# ESP32_breakout_v2.net
KiCad netlist of a schematic drawn in EAGLE
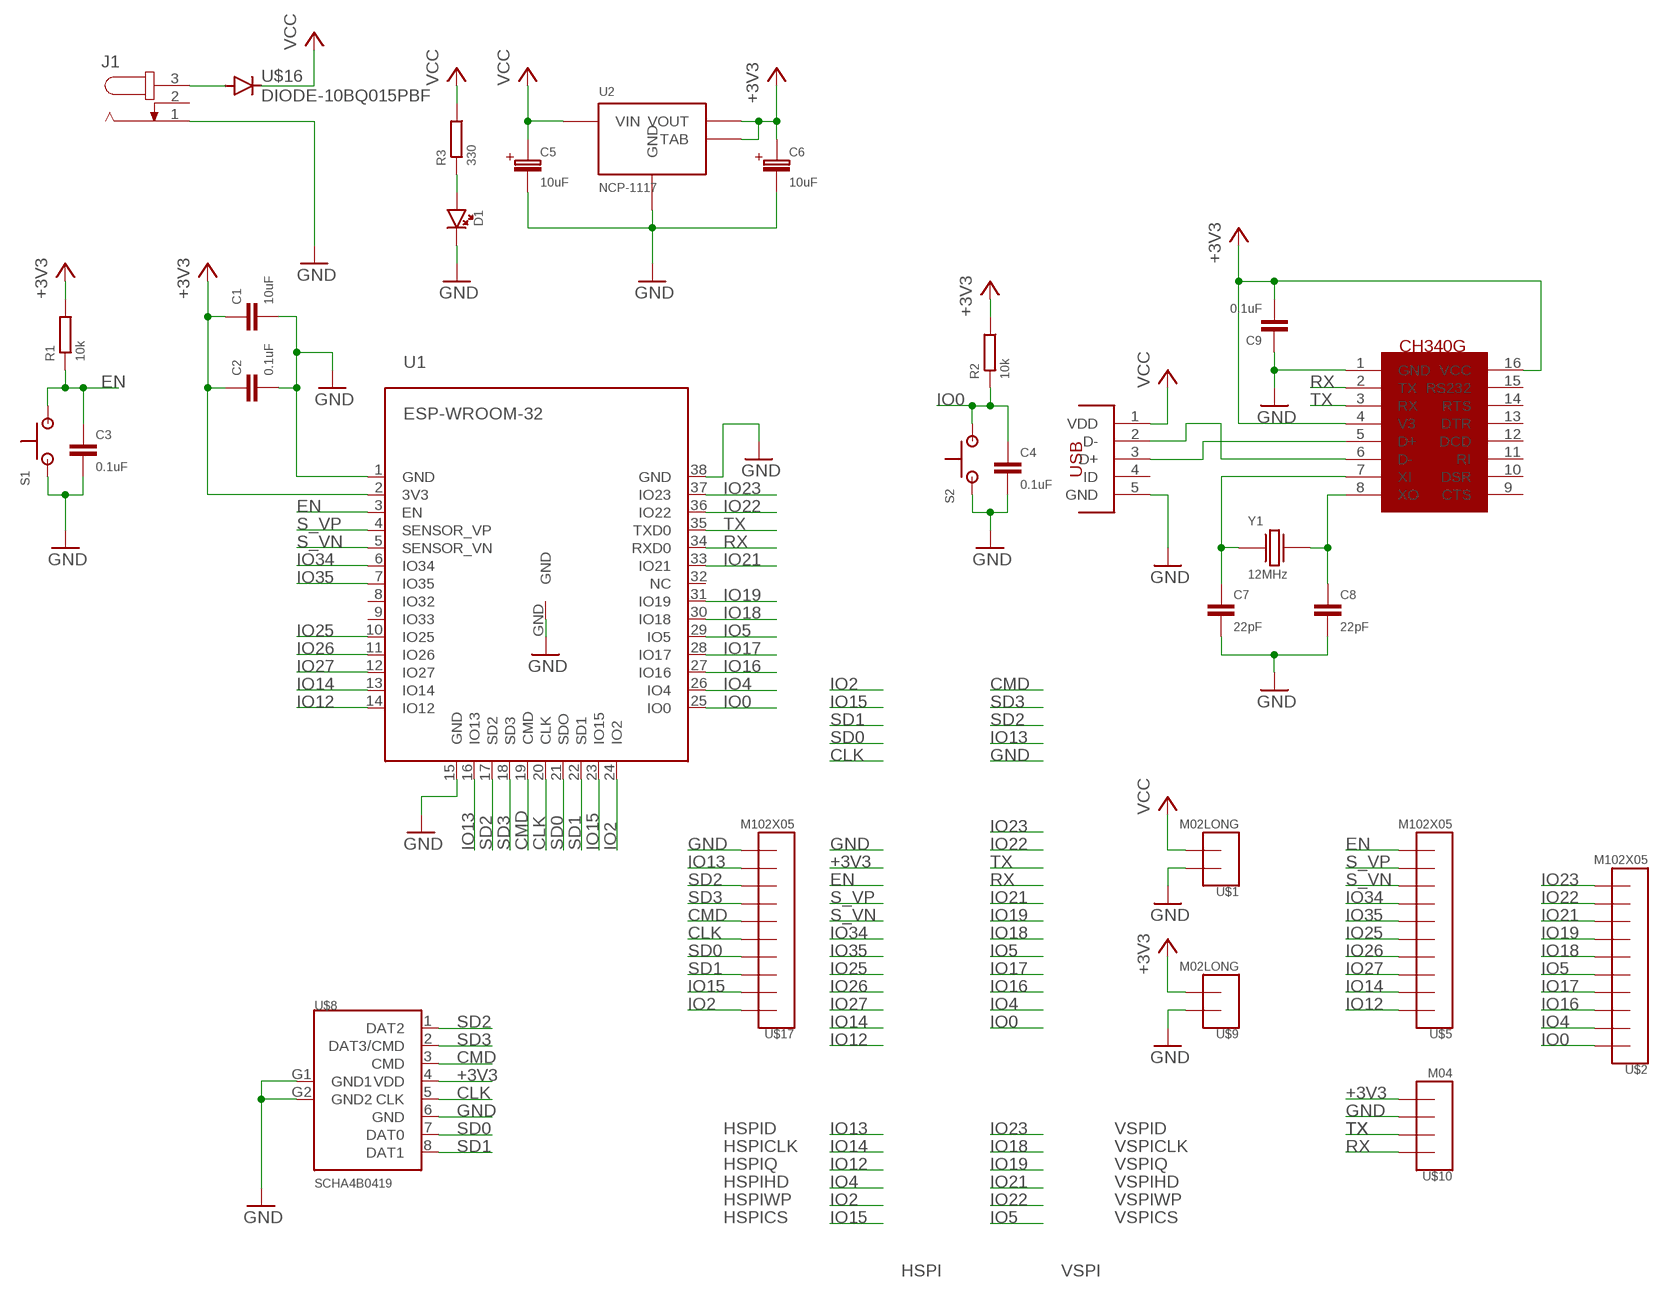
[diagram p0: schematic, sheet 1]

(export (version "E")
  (design (tool "Eeschema 10.0.6"))
  (components
    (comp (ref "C1")
      (value "10uF")
      (footprint "eagle-import:CAP-0603")
      (libsource (lib "eagle-import") (part "CAP0603"))
    )
    (comp (ref "C2")
      (value "0.1uF")
      (footprint "eagle-import:CAP-0603")
      (libsource (lib "eagle-import") (part "CAP0603"))
    )
    (comp (ref "C3")
      (value "0.1uF")
      (footprint "eagle-import:CAP-0603")
      (libsource (lib "eagle-import") (part "CAP0603"))
    )
    (comp (ref "C4")
      (value "0.1uF")
      (footprint "eagle-import:CAP-0603")
      (libsource (lib "eagle-import") (part "CAP0603"))
    )
    (comp (ref "C5")
      (value "10uF")
      (footprint "eagle-import:B-3528")
      (libsource (lib "eagle-import") (part "CAP-POLARCASEB-3528"))
    )
    (comp (ref "C6")
      (value "10uF")
      (footprint "eagle-import:B-3528")
      (libsource (lib "eagle-import") (part "CAP-POLARCASEB-3528"))
    )
    (comp (ref "C7")
      (value "22pF")
      (footprint "eagle-import:CAP-0603")
      (libsource (lib "eagle-import") (part "CAP0603"))
    )
    (comp (ref "C8")
      (value "22pF")
      (footprint "eagle-import:CAP-0603")
      (libsource (lib "eagle-import") (part "CAP0603"))
    )
    (comp (ref "C9")
      (value "0.1uF")
      (footprint "eagle-import:CAP-0603")
      (libsource (lib "eagle-import") (part "CAP0603"))
    )
    (comp (ref "D1")
      (value "LED1206")
      (footprint "eagle-import:LED-1206")
      (libsource (lib "eagle-import") (part "LED1206"))
    )
    (comp (ref "J1")
      (value "JACK-PLUG0")
      (footprint "eagle-import:SPC4077")
      (libsource (lib "eagle-import") (part "JACK-PLUG0"))
    )
    (comp (ref "R1")
      (value "10k")
      (footprint "eagle-import:RES-0603")
      (libsource (lib "eagle-import") (part "RESISTOR0603"))
    )
    (comp (ref "R2")
      (value "10k")
      (footprint "eagle-import:RES-0603")
      (libsource (lib "eagle-import") (part "RESISTOR0603"))
    )
    (comp (ref "R3")
      (value "330")
      (footprint "eagle-import:RES-0603")
      (libsource (lib "eagle-import") (part "RESISTOR0603"))
    )
    (comp (ref "S1")
      (value "PUSHBUTTONSKHMQME010")
      (footprint "eagle-import:SKHMQME010")
      (libsource (lib "eagle-import") (part "PUSHBUTTONSKHMQME010"))
    )
    (comp (ref "S2")
      (value "PUSHBUTTONSKHMQME010")
      (footprint "eagle-import:SKHMQME010")
      (libsource (lib "eagle-import") (part "PUSHBUTTONSKHMQME010"))
    )
    (comp (ref "U$1")
      (value "M02LONG")
      (footprint "eagle-import:1X02-LONG")
      (libsource (lib "eagle-import") (part "M02LONG"))
    )
    (comp (ref "U$2")
      (value "M102X05")
      (footprint "eagle-import:2X05")
      (libsource (lib "eagle-import") (part "M102X05"))
    )
    (comp (ref "U$4")
      (value "MOLEX_USBMICRO")
      (footprint "eagle-import:MOLEX_47346-001")
      (libsource (lib "eagle-import") (part "MOLEX_USBMICRO"))
    )
    (comp (ref "U$5")
      (value "M102X05")
      (footprint "eagle-import:2X05")
      (libsource (lib "eagle-import") (part "M102X05"))
    )
    (comp (ref "U$7")
      (value "CH340G")
      (footprint "eagle-import:SOIC16")
      (libsource (lib "eagle-import") (part "CH340G"))
    )
    (comp (ref "U$8")
      (value "SCHA4B0419")
      (footprint "eagle-import:MICROSD_SCHA4B0419")
      (libsource (lib "eagle-import") (part "SCHA4B0419"))
    )
    (comp (ref "U$9")
      (value "M02LONG")
      (footprint "eagle-import:1X02-LONG")
      (libsource (lib "eagle-import") (part "M02LONG"))
    )
    (comp (ref "U$10")
      (value "M04")
      (footprint "eagle-import:1X04")
      (libsource (lib "eagle-import") (part "M04"))
    )
    (comp (ref "U$16")
      (value "DIODE-10BQ015PBF")
      (footprint "eagle-import:10BQ015PB")
      (libsource (lib "eagle-import") (part "DIODE-10BQ015PBF"))
    )
    (comp (ref "U$17")
      (value "M102X05")
      (footprint "eagle-import:2X05")
      (libsource (lib "eagle-import") (part "M102X05"))
    )
    (comp (ref "U1")
      (value "ESP-WROOM-32")
      (footprint "eagle-import:ESP-WROOM-32")
      (libsource (lib "eagle-import") (part "ESP-WROOM-32"))
    )
    (comp (ref "U2")
      (value "NCP-1117")
      (footprint "eagle-import:SOT-223-4")
      (libsource (lib "eagle-import") (part "NCP-1117"))
    )
    (comp (ref "Y1")
      (value "12MHz")
      (footprint "eagle-import:HC-49_US")
      (libsource (lib "eagle-import") (part "ABLS-12MHZ-B2-T"))
    )
  )
  (nets
    (net (code "1") (name "+3V3") (class "Default")
      (node (ref "C1") (pin "1") (pinfunction "1_1") (pintype "passive"))
      (node (ref "C2") (pin "1") (pinfunction "1_1") (pintype "passive"))
      (node (ref "C6") (pin "P") (pinfunction "P_P") (pintype "passive"))
      (node (ref "C9") (pin "2") (pinfunction "2_2") (pintype "passive"))
      (node (ref "R1") (pin "2") (pinfunction "2_2") (pintype "passive"))
      (node (ref "R2") (pin "2") (pinfunction "2_2") (pintype "passive"))
      (node (ref "U$10") (pin "4") (pinfunction "4_4") (pintype "bidirectional"))
      (node (ref "U$7") (pin "16") (pinfunction "VCC_16") (pintype "bidirectional"))
      (node (ref "U$7") (pin "4") (pinfunction "V3_4") (pintype "bidirectional"))
      (node (ref "U$8") (pin "4") (pinfunction "VDD_4") (pintype "bidirectional"))
      (node (ref "U$9") (pin "2") (pinfunction "2_2") (pintype "bidirectional"))
      (node (ref "U1") (pin "2") (pinfunction "3V3_2") (pintype "bidirectional"))
      (node (ref "U2") (pin "2") (pinfunction "VOUT_2") (pintype "power_in"))
      (node (ref "U2") (pin "PAD") (pinfunction "TAB_PAD") (pintype "power_in"))
    )
    (net (code "2") (name "/CLK") (class "Default")
      (node (ref "U$17") (pin "5") (pinfunction "5_5") (pintype "bidirectional"))
      (node (ref "U$8") (pin "5") (pinfunction "CLK_5") (pintype "bidirectional"))
      (node (ref "U1") (pin "20") (pinfunction "CLK_20") (pintype "bidirectional"))
    )
    (net (code "3") (name "/CMD") (class "Default")
      (node (ref "U$17") (pin "6") (pinfunction "6_6") (pintype "bidirectional"))
      (node (ref "U$8") (pin "3") (pinfunction "CMD_3") (pintype "bidirectional"))
      (node (ref "U1") (pin "19") (pinfunction "CMD_19") (pintype "bidirectional"))
    )
    (net (code "4") (name "/EN") (class "Default")
      (node (ref "C3") (pin "1") (pinfunction "1_1") (pintype "passive"))
      (node (ref "R1") (pin "1") (pinfunction "1_1") (pintype "passive"))
      (node (ref "S1") (pin "3") (pinfunction "2_3") (pintype "bidirectional"))
      (node (ref "S1") (pin "4") (pinfunction "2_4") (pintype "bidirectional"))
      (node (ref "U$5") (pin "10") (pinfunction "10_10") (pintype "bidirectional"))
      (node (ref "U1") (pin "3") (pinfunction "EN_3") (pintype "bidirectional"))
    )
    (net (code "5") (name "/IO0") (class "Default")
      (node (ref "C4") (pin "1") (pinfunction "1_1") (pintype "passive"))
      (node (ref "R2") (pin "1") (pinfunction "1_1") (pintype "passive"))
      (node (ref "S2") (pin "3") (pinfunction "2_3") (pintype "bidirectional"))
      (node (ref "S2") (pin "4") (pinfunction "2_4") (pintype "bidirectional"))
      (node (ref "U$2") (pin "1") (pinfunction "1_1") (pintype "bidirectional"))
      (node (ref "U1") (pin "25") (pinfunction "IO0_25") (pintype "bidirectional"))
    )
    (net (code "6") (name "/IO2") (class "Default")
      (node (ref "U$17") (pin "1") (pinfunction "1_1") (pintype "bidirectional"))
      (node (ref "U1") (pin "24") (pinfunction "IO2_24") (pintype "bidirectional"))
    )
    (net (code "7") (name "/IO4") (class "Default")
      (node (ref "U$2") (pin "2") (pinfunction "2_2") (pintype "bidirectional"))
      (node (ref "U1") (pin "26") (pinfunction "IO4_26") (pintype "bidirectional"))
    )
    (net (code "8") (name "/IO5") (class "Default")
      (node (ref "U$2") (pin "5") (pinfunction "5_5") (pintype "bidirectional"))
      (node (ref "U1") (pin "29") (pinfunction "IO5_29") (pintype "bidirectional"))
    )
    (net (code "9") (name "/IO12") (class "Default")
      (node (ref "U$5") (pin "1") (pinfunction "1_1") (pintype "bidirectional"))
      (node (ref "U1") (pin "14") (pinfunction "IO12_14") (pintype "bidirectional"))
    )
    (net (code "10") (name "/IO13") (class "Default")
      (node (ref "U$17") (pin "9") (pinfunction "9_9") (pintype "bidirectional"))
      (node (ref "U1") (pin "16") (pinfunction "IO13_16") (pintype "bidirectional"))
    )
    (net (code "11") (name "/IO14") (class "Default")
      (node (ref "U$5") (pin "2") (pinfunction "2_2") (pintype "bidirectional"))
      (node (ref "U1") (pin "13") (pinfunction "IO14_13") (pintype "bidirectional"))
    )
    (net (code "12") (name "/IO15") (class "Default")
      (node (ref "U$17") (pin "2") (pinfunction "2_2") (pintype "bidirectional"))
      (node (ref "U1") (pin "23") (pinfunction "IO15_23") (pintype "bidirectional"))
    )
    (net (code "13") (name "/IO16") (class "Default")
      (node (ref "U$2") (pin "3") (pinfunction "3_3") (pintype "bidirectional"))
      (node (ref "U1") (pin "27") (pinfunction "IO16_27") (pintype "bidirectional"))
    )
    (net (code "14") (name "/IO17") (class "Default")
      (node (ref "U$2") (pin "4") (pinfunction "4_4") (pintype "bidirectional"))
      (node (ref "U1") (pin "28") (pinfunction "IO17_28") (pintype "bidirectional"))
    )
    (net (code "15") (name "/IO18") (class "Default")
      (node (ref "U$2") (pin "6") (pinfunction "6_6") (pintype "bidirectional"))
      (node (ref "U1") (pin "30") (pinfunction "IO18_30") (pintype "bidirectional"))
    )
    (net (code "16") (name "/IO19") (class "Default")
      (node (ref "U$2") (pin "7") (pinfunction "7_7") (pintype "bidirectional"))
      (node (ref "U1") (pin "31") (pinfunction "IO19_31") (pintype "bidirectional"))
    )
    (net (code "17") (name "/IO21") (class "Default")
      (node (ref "U$2") (pin "8") (pinfunction "8_8") (pintype "bidirectional"))
      (node (ref "U1") (pin "33") (pinfunction "IO21_33") (pintype "bidirectional"))
    )
    (net (code "18") (name "/IO22") (class "Default")
      (node (ref "U$2") (pin "9") (pinfunction "9_9") (pintype "bidirectional"))
      (node (ref "U1") (pin "36") (pinfunction "IO22_36") (pintype "bidirectional"))
    )
    (net (code "19") (name "/IO23") (class "Default")
      (node (ref "U$2") (pin "10") (pinfunction "10_10") (pintype "bidirectional"))
      (node (ref "U1") (pin "37") (pinfunction "IO23_37") (pintype "bidirectional"))
    )
    (net (code "20") (name "/IO25") (class "Default")
      (node (ref "U$5") (pin "5") (pinfunction "5_5") (pintype "bidirectional"))
      (node (ref "U1") (pin "10") (pinfunction "IO25_10") (pintype "bidirectional"))
    )
    (net (code "21") (name "/IO26") (class "Default")
      (node (ref "U$5") (pin "4") (pinfunction "4_4") (pintype "bidirectional"))
      (node (ref "U1") (pin "11") (pinfunction "IO26_11") (pintype "bidirectional"))
    )
    (net (code "22") (name "/IO27") (class "Default")
      (node (ref "U$5") (pin "3") (pinfunction "3_3") (pintype "bidirectional"))
      (node (ref "U1") (pin "12") (pinfunction "IO27_12") (pintype "bidirectional"))
    )
    (net (code "23") (name "/IO34") (class "Default")
      (node (ref "U$5") (pin "7") (pinfunction "7_7") (pintype "bidirectional"))
      (node (ref "U1") (pin "6") (pinfunction "IO34_6") (pintype "bidirectional"))
    )
    (net (code "24") (name "/IO35") (class "Default")
      (node (ref "U$5") (pin "6") (pinfunction "6_6") (pintype "bidirectional"))
      (node (ref "U1") (pin "7") (pinfunction "IO35_7") (pintype "bidirectional"))
    )
    (net (code "25") (name "/RX") (class "Default")
      (node (ref "U$10") (pin "1") (pinfunction "1_1") (pintype "bidirectional"))
      (node (ref "U$7") (pin "2") (pinfunction "TX_2") (pintype "bidirectional"))
      (node (ref "U1") (pin "34") (pinfunction "RXD0_34") (pintype "bidirectional"))
    )
    (net (code "26") (name "/SD0") (class "Default")
      (node (ref "U$17") (pin "4") (pinfunction "4_4") (pintype "bidirectional"))
      (node (ref "U$8") (pin "7") (pinfunction "DAT0_7") (pintype "bidirectional"))
      (node (ref "U1") (pin "21") (pinfunction "SDO_21") (pintype "bidirectional"))
    )
    (net (code "27") (name "/SD1") (class "Default")
      (node (ref "U$17") (pin "3") (pinfunction "3_3") (pintype "bidirectional"))
      (node (ref "U$8") (pin "8") (pinfunction "DAT1_8") (pintype "bidirectional"))
      (node (ref "U1") (pin "22") (pinfunction "SD1_22") (pintype "bidirectional"))
    )
    (net (code "28") (name "/SD2") (class "Default")
      (node (ref "U$17") (pin "8") (pinfunction "8_8") (pintype "bidirectional"))
      (node (ref "U$8") (pin "1") (pinfunction "DAT2_1") (pintype "bidirectional"))
      (node (ref "U1") (pin "17") (pinfunction "SD2_17") (pintype "bidirectional"))
    )
    (net (code "29") (name "/SD3") (class "Default")
      (node (ref "U$17") (pin "7") (pinfunction "7_7") (pintype "bidirectional"))
      (node (ref "U$8") (pin "2") (pinfunction "DAT3/CMD_2") (pintype "bidirectional"))
      (node (ref "U1") (pin "18") (pinfunction "SD3_18") (pintype "bidirectional"))
    )
    (net (code "30") (name "/S_VN") (class "Default")
      (node (ref "U$5") (pin "8") (pinfunction "8_8") (pintype "bidirectional"))
      (node (ref "U1") (pin "5") (pinfunction "SENSOR_VN_5") (pintype "bidirectional"))
    )
    (net (code "31") (name "/S_VP") (class "Default")
      (node (ref "U$5") (pin "9") (pinfunction "9_9") (pintype "bidirectional"))
      (node (ref "U1") (pin "4") (pinfunction "SENSOR_VP_4") (pintype "bidirectional"))
    )
    (net (code "32") (name "/TX") (class "Default")
      (node (ref "U$10") (pin "2") (pinfunction "2_2") (pintype "bidirectional"))
      (node (ref "U$7") (pin "3") (pinfunction "RX_3") (pintype "bidirectional"))
      (node (ref "U1") (pin "35") (pinfunction "TXD0_35") (pintype "bidirectional"))
    )
    (net (code "33") (name "GND") (class "Default")
      (node (ref "C1") (pin "2") (pinfunction "2_2") (pintype "passive"))
      (node (ref "C2") (pin "2") (pinfunction "2_2") (pintype "passive"))
      (node (ref "C3") (pin "2") (pinfunction "2_2") (pintype "passive"))
      (node (ref "C4") (pin "2") (pinfunction "2_2") (pintype "passive"))
      (node (ref "C5") (pin "N") (pinfunction "N_N") (pintype "passive"))
      (node (ref "C6") (pin "N") (pinfunction "N_N") (pintype "passive"))
      (node (ref "C7") (pin "2") (pinfunction "2_2") (pintype "passive"))
      (node (ref "C8") (pin "2") (pinfunction "2_2") (pintype "passive"))
      (node (ref "C9") (pin "1") (pinfunction "1_1") (pintype "passive"))
      (node (ref "D1") (pin "C") (pinfunction "C_C") (pintype "bidirectional"))
      (node (ref "J1") (pin "1") (pinfunction "1_1") (pintype "passive"))
      (node (ref "S1") (pin "1") (pinfunction "1_1") (pintype "bidirectional"))
      (node (ref "S1") (pin "2") (pinfunction "1_2") (pintype "bidirectional"))
      (node (ref "S2") (pin "1") (pinfunction "1_1") (pintype "bidirectional"))
      (node (ref "S2") (pin "2") (pinfunction "1_2") (pintype "bidirectional"))
      (node (ref "U$1") (pin "1") (pinfunction "1_1") (pintype "bidirectional"))
      (node (ref "U$10") (pin "3") (pinfunction "3_3") (pintype "bidirectional"))
      (node (ref "U$17") (pin "10") (pinfunction "10_10") (pintype "bidirectional"))
      (node (ref "U$4") (pin "5") (pinfunction "GND_5") (pintype "bidirectional"))
      (node (ref "U$7") (pin "1") (pinfunction "GND_1") (pintype "bidirectional"))
      (node (ref "U$8") (pin "6") (pinfunction "GND_6") (pintype "bidirectional"))
      (node (ref "U$8") (pin "G1") (pinfunction "GND1_G1") (pintype "bidirectional"))
      (node (ref "U$8") (pin "G2") (pinfunction "GND2_G2") (pintype "bidirectional"))
      (node (ref "U$9") (pin "1") (pinfunction "1_1") (pintype "bidirectional"))
      (node (ref "U1") (pin "1") (pinfunction "GND_1") (pintype "bidirectional"))
      (node (ref "U1") (pin "15") (pinfunction "GND_15") (pintype "bidirectional"))
      (node (ref "U1") (pin "38") (pinfunction "GND_38") (pintype "bidirectional"))
      (node (ref "U1") (pin "GND") (pinfunction "GND_GND") (pintype "bidirectional"))
      (node (ref "U2") (pin "1") (pinfunction "GND_1") (pintype "power_in"))
    )
    (net (code "34") (name "Net-(D1-PadA)") (class "Default")
      (node (ref "D1") (pin "A") (pinfunction "A_A") (pintype "bidirectional"))
      (node (ref "R3") (pin "1") (pinfunction "1_1") (pintype "passive"))
    )
    (net (code "35") (name "Net-(J1-Pad3)") (class "Default")
      (node (ref "J1") (pin "3") (pinfunction "3_3") (pintype "passive"))
      (node (ref "U$16") (pin "A") (pinfunction "A_A") (pintype "passive"))
    )
    (net (code "36") (name "Net-(U$4-D+)") (class "Default")
      (node (ref "U$4") (pin "3") (pinfunction "D+_3") (pintype "bidirectional"))
      (node (ref "U$7") (pin "5") (pinfunction "D+_5") (pintype "bidirectional"))
    )
    (net (code "37") (name "Net-(U$4-D-)") (class "Default")
      (node (ref "U$4") (pin "2") (pinfunction "D-_2") (pintype "bidirectional"))
      (node (ref "U$7") (pin "6") (pinfunction "D-_6") (pintype "bidirectional"))
    )
    (net (code "38") (name "Net-(U$7-XI)") (class "Default")
      (node (ref "C7") (pin "1") (pinfunction "1_1") (pintype "passive"))
      (node (ref "U$7") (pin "7") (pinfunction "XI_7") (pintype "bidirectional"))
      (node (ref "Y1") (pin "P$1") (pinfunction "1_P$1") (pintype "bidirectional"))
    )
    (net (code "39") (name "Net-(U$7-XO)") (class "Default")
      (node (ref "C8") (pin "1") (pinfunction "1_1") (pintype "passive"))
      (node (ref "U$7") (pin "8") (pinfunction "XO_8") (pintype "bidirectional"))
      (node (ref "Y1") (pin "P$2") (pinfunction "2_P$2") (pintype "bidirectional"))
    )
    (net (code "40") (name "VCC") (class "Default")
      (node (ref "C5") (pin "P") (pinfunction "P_P") (pintype "passive"))
      (node (ref "R3") (pin "2") (pinfunction "2_2") (pintype "passive"))
      (node (ref "U$1") (pin "2") (pinfunction "2_2") (pintype "bidirectional"))
      (node (ref "U$16") (pin "C") (pinfunction "C_C") (pintype "passive"))
      (node (ref "U$4") (pin "1") (pinfunction "VDD_1") (pintype "bidirectional"))
      (node (ref "U2") (pin "3") (pinfunction "VIN_3") (pintype "power_in"))
    )
    (net (code "41") (name "unconnected-(J1-Pad2)") (class "Default")
      (node (ref "J1") (pin "2") (pinfunction "2_2") (pintype "passive"))
    )
    (net (code "42") (name "unconnected-(S1-3-Pad5)") (class "Default")
      (node (ref "S1") (pin "5") (pinfunction "3_5") (pintype "bidirectional"))
    )
    (net (code "43") (name "unconnected-(S2-3-Pad5)") (class "Default")
      (node (ref "S2") (pin "5") (pinfunction "3_5") (pintype "bidirectional"))
    )
    (net (code "44") (name "unconnected-(U$4-ID-Pad4)") (class "Default")
      (node (ref "U$4") (pin "4") (pinfunction "ID_4") (pintype "bidirectional"))
    )
    (net (code "45") (name "unconnected-(U$7-CTS-Pad9)") (class "Default")
      (node (ref "U$7") (pin "9") (pinfunction "CTS_9") (pintype "bidirectional"))
    )
    (net (code "46") (name "unconnected-(U$7-DCD-Pad12)") (class "Default")
      (node (ref "U$7") (pin "12") (pinfunction "DCD_12") (pintype "bidirectional"))
    )
    (net (code "47") (name "unconnected-(U$7-DSR-Pad10)") (class "Default")
      (node (ref "U$7") (pin "10") (pinfunction "DSR_10") (pintype "bidirectional"))
    )
    (net (code "48") (name "unconnected-(U$7-DTR-Pad13)") (class "Default")
      (node (ref "U$7") (pin "13") (pinfunction "DTR_13") (pintype "bidirectional"))
    )
    (net (code "49") (name "unconnected-(U$7-RI-Pad11)") (class "Default")
      (node (ref "U$7") (pin "11") (pinfunction "RI_11") (pintype "bidirectional"))
    )
    (net (code "50") (name "unconnected-(U$7-RS232-Pad15)") (class "Default")
      (node (ref "U$7") (pin "15") (pinfunction "RS232_15") (pintype "bidirectional"))
    )
    (net (code "51") (name "unconnected-(U$7-RTS-Pad14)") (class "Default")
      (node (ref "U$7") (pin "14") (pinfunction "RTS_14") (pintype "bidirectional"))
    )
    (net (code "52") (name "unconnected-(U1-IO32-Pad8)") (class "Default")
      (node (ref "U1") (pin "8") (pinfunction "IO32_8") (pintype "bidirectional"))
    )
    (net (code "53") (name "unconnected-(U1-IO33-Pad9)") (class "Default")
      (node (ref "U1") (pin "9") (pinfunction "IO33_9") (pintype "bidirectional"))
    )
    (net (code "54") (name "unconnected-(U1-NC-Pad32)") (class "Default")
      (node (ref "U1") (pin "32") (pinfunction "NC_32") (pintype "bidirectional"))
    )
  )
)
